# schemat.net
KiCad netlist of a schematic drawn in Altium Designer
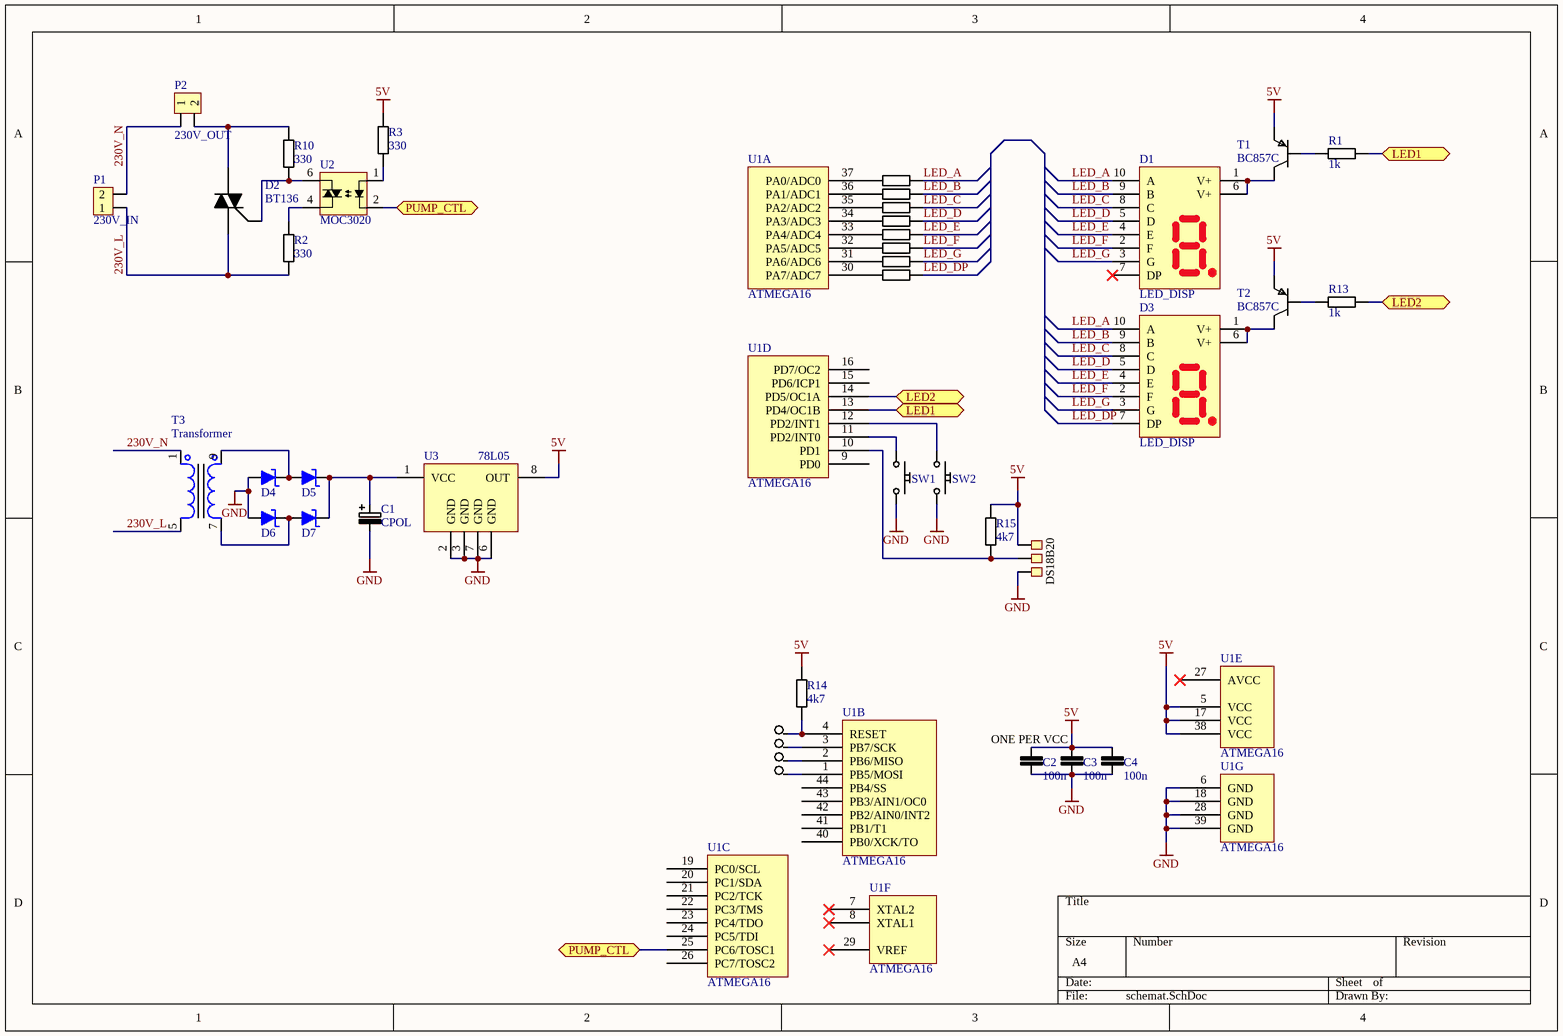
[diagram p0: schemat.SchDoc]

(export (version "E")
  (design (tool "Eeschema 10.0.6"))
  (components
    (comp (ref "C1") (value "CPOL") (footprint "Cap10/5mm") (libsource (lib "A4WP") (part "CPOL")))
    (comp (ref "C2")
      (value "100n")
      (footprint "0805C")
      (description "Kondensator")
      (libsource (lib "iMed24") (part "C"))
    )
    (comp (ref "C3")
      (value "100n")
      (footprint "0805C")
      (description "Kondensator")
      (libsource (lib "iMed24") (part "C"))
    )
    (comp (ref "C4")
      (value "100n")
      (footprint "0805C")
      (description "Kondensator")
      (libsource (lib "iMed24") (part "C"))
    )
    (comp (ref "D1")
      (value "LED_DISP")
      (footprint "LED_DISP")
      (libsource (lib "BibliotekiAltium") (part "LED_DISP"))
    )
    (comp (ref "D2") (value "BT136") (footprint "TO220") (libsource (lib "BibliotekiAltium") (part "BT136")))
    (comp (ref "D3")
      (value "LED_DISP")
      (footprint "LED_DISP")
      (libsource (lib "BibliotekiAltium") (part "LED_DISP"))
    )
    (comp (ref "D4") (value "Schottky") (footprint "SOD128") (libsource (lib "gan_mgr") (part "Schottky")))
    (comp (ref "D5") (value "Schottky") (footprint "SOD128") (libsource (lib "gan_mgr") (part "Schottky")))
    (comp (ref "D6") (value "Schottky") (footprint "SOD128") (libsource (lib "gan_mgr") (part "Schottky")))
    (comp (ref "D7") (value "Schottky") (footprint "SOD128") (libsource (lib "gan_mgr") (part "Schottky")))
    (comp (ref "P1")
      (value "230V_IN")
      (footprint "ARK2")
      (description "5mm")
      (libsource (lib "gan_mgr") (part "ARK2"))
    )
    (comp (ref "P2")
      (value "230V_OUT")
      (footprint "ARK2")
      (description "5mm")
      (libsource (lib "") (part "ARK2_1"))
    )
    (comp (ref "P3") (value "PAD") (footprint "PAD1.5") (libsource (lib "KWP") (part "PAD")))
    (comp (ref "P4") (value "PAD") (footprint "PAD1.5") (libsource (lib "KWP") (part "PAD")))
    (comp (ref "P5") (value "PAD") (footprint "PAD1.5") (libsource (lib "KWP") (part "PAD")))
    (comp (ref "P6") (value "PAD") (footprint "PAD1.5") (libsource (lib "KWP") (part "PAD")))
    (comp (ref "P7")
      (value "PAD_THT")
      (footprint "PAD_0.8mm")
      (libsource (lib "BibliotekiAltium") (part "PAD_THT"))
    )
    (comp (ref "P8")
      (value "PAD_THT")
      (footprint "PAD_0.8mm")
      (libsource (lib "BibliotekiAltium") (part "PAD_THT"))
    )
    (comp (ref "P9")
      (value "PAD_THT")
      (footprint "PAD_0.8mm")
      (libsource (lib "BibliotekiAltium") (part "PAD_THT"))
    )
    (comp (ref "R1")
      (value "1k")
      (footprint "0805R")
      (description "Rezystor")
      (libsource (lib "iMed24") (part "R"))
    )
    (comp (ref "R2")
      (value "330")
      (footprint "0805R")
      (description "Rezystor")
      (libsource (lib "") (part "R_1"))
    )
    (comp (ref "R3")
      (value "330")
      (footprint "0805R")
      (description "Rezystor")
      (libsource (lib "iMed24") (part "R"))
    )
    (comp (ref "R4")
      (value "220")
      (footprint "0805R")
      (description "Rezystor")
      (libsource (lib "iMed24") (part "R"))
    )
    (comp (ref "R5")
      (value "220")
      (footprint "0805R")
      (description "Rezystor")
      (libsource (lib "iMed24") (part "R"))
    )
    (comp (ref "R6")
      (value "220")
      (footprint "0805R")
      (description "Rezystor")
      (libsource (lib "iMed24") (part "R"))
    )
    (comp (ref "R7")
      (value "220")
      (footprint "0805R")
      (description "Rezystor")
      (libsource (lib "iMed24") (part "R"))
    )
    (comp (ref "R8")
      (value "220")
      (footprint "0805R")
      (description "Rezystor")
      (libsource (lib "iMed24") (part "R"))
    )
    (comp (ref "R9")
      (value "220")
      (footprint "0805R")
      (description "Rezystor")
      (libsource (lib "iMed24") (part "R"))
    )
    (comp (ref "R10")
      (value "330")
      (footprint "0805R")
      (description "Rezystor")
      (libsource (lib "") (part "R_1"))
    )
    (comp (ref "R11")
      (value "220")
      (footprint "0805R")
      (description "Rezystor")
      (libsource (lib "iMed24") (part "R"))
    )
    (comp (ref "R12")
      (value "220")
      (footprint "0805R")
      (description "Rezystor")
      (libsource (lib "iMed24") (part "R"))
    )
    (comp (ref "R13")
      (value "1k")
      (footprint "0805R")
      (description "Rezystor")
      (libsource (lib "iMed24") (part "R"))
    )
    (comp (ref "R14")
      (value "4k7")
      (footprint "0805R")
      (description "Rezystor")
      (libsource (lib "") (part "R_1"))
    )
    (comp (ref "R15")
      (value "4k7")
      (footprint "0805R")
      (description "Rezystor")
      (libsource (lib "") (part "R_1"))
    )
    (comp (ref "SW1")
      (value "SW 5mm 1,5N SMD")
      (footprint "SW5SMD")
      (description "Microswitch")
      (libsource (lib "iMed24") (part "SW 5mm 1,5N SMD"))
    )
    (comp (ref "SW2")
      (value "SW 5mm 1,5N SMD")
      (footprint "SW5SMD")
      (description "Microswitch")
      (libsource (lib "iMed24") (part "SW 5mm 1,5N SMD"))
    )
    (comp (ref "T1")
      (value "BC857C")
      (footprint "SOT23-3")
      (description "PNP (45V/0.1A)")
      (libsource (lib "Transistor") (part "BC857C"))
    )
    (comp (ref "T2")
      (value "BC857C")
      (footprint "SOT23-3")
      (description "PNP (45V/0.1A)")
      (libsource (lib "Transistor") (part "BC857C"))
    )
    (comp (ref "T3")
      (value "Transformer")
      (footprint "TSZZ4.5/017M")
      (libsource (lib "BibliotekiAltium") (part "Transformer"))
    )
    (comp (ref "U1")
      (value "ATMEGA16")
      (footprint "TQFP44")
      (libsource (lib "BibliotekiAltium") (part "ATMEGA16"))
    )
    (comp (ref "U2")
      (value "MOC3020")
      (footprint "DIP6")
      (libsource (lib "BibliotekiAltium") (part "MOC3020"))
    )
    (comp (ref "U3") (value "78L05") (footprint "SOIC8") (libsource (lib "BibliotekiAltium") (part "78L05")))
  )
  (nets
    (net (code "1") (name "/230V_L") (class "Default")
      (node (ref "D2") (pin "1") (pinfunction "T1_1") (pintype "passive"))
      (node (ref "P1") (pin "1") (pinfunction "1_1") (pintype "passive"))
      (node (ref "R2") (pin "2") (pinfunction "2_2") (pintype "passive"))
      (node (ref "T3") (pin "5") (pinfunction "5_5") (pintype "passive"))
    )
    (net (code "2") (name "/230V_N") (class "Default")
      (node (ref "P1") (pin "2") (pinfunction "2_2") (pintype "passive"))
      (node (ref "P2") (pin "1") (pinfunction "1_1") (pintype "passive"))
      (node (ref "T3") (pin "1") (pinfunction "1_1") (pintype "passive"))
    )
    (net (code "3") (name "/LED1") (class "Default")
      (node (ref "R1") (pin "2") (pinfunction "2_2") (pintype "passive"))
      (node (ref "U1") (pin "13") (pinfunction "PD4/OC1B_13") (pintype "passive"))
    )
    (net (code "4") (name "/LED2") (class "Default")
      (node (ref "R13") (pin "2") (pinfunction "2_2") (pintype "passive"))
      (node (ref "U1") (pin "14") (pinfunction "PD5/OC1A_14") (pintype "passive"))
    )
    (net (code "5") (name "/LED_A") (class "Default")
      (node (ref "D1") (pin "10") (pinfunction "A_10") (pintype "passive"))
      (node (ref "D3") (pin "10") (pinfunction "A_10") (pintype "passive"))
      (node (ref "R4") (pin "2") (pinfunction "2_2") (pintype "passive"))
    )
    (net (code "6") (name "/LED_B") (class "Default")
      (node (ref "D1") (pin "9") (pinfunction "B_9") (pintype "passive"))
      (node (ref "D3") (pin "9") (pinfunction "B_9") (pintype "passive"))
      (node (ref "R5") (pin "2") (pinfunction "2_2") (pintype "passive"))
    )
    (net (code "7") (name "/LED_C") (class "Default")
      (node (ref "D1") (pin "8") (pinfunction "C_8") (pintype "passive"))
      (node (ref "D3") (pin "8") (pinfunction "C_8") (pintype "passive"))
      (node (ref "R6") (pin "2") (pinfunction "2_2") (pintype "passive"))
    )
    (net (code "8") (name "/LED_D") (class "Default")
      (node (ref "D1") (pin "5") (pinfunction "D_5") (pintype "passive"))
      (node (ref "D3") (pin "5") (pinfunction "D_5") (pintype "passive"))
      (node (ref "R7") (pin "2") (pinfunction "2_2") (pintype "passive"))
    )
    (net (code "9") (name "/LED_DP") (class "Default")
      (node (ref "D3") (pin "7") (pinfunction "DP_7") (pintype "passive"))
      (node (ref "R12") (pin "2") (pinfunction "2_2") (pintype "passive"))
    )
    (net (code "10") (name "/LED_E") (class "Default")
      (node (ref "D1") (pin "4") (pinfunction "E_4") (pintype "passive"))
      (node (ref "D3") (pin "4") (pinfunction "E_4") (pintype "passive"))
      (node (ref "R8") (pin "2") (pinfunction "2_2") (pintype "passive"))
    )
    (net (code "11") (name "/LED_F") (class "Default")
      (node (ref "D1") (pin "2") (pinfunction "F_2") (pintype "passive"))
      (node (ref "D3") (pin "2") (pinfunction "F_2") (pintype "passive"))
      (node (ref "R9") (pin "2") (pinfunction "2_2") (pintype "passive"))
    )
    (net (code "12") (name "/LED_G") (class "Default")
      (node (ref "D1") (pin "3") (pinfunction "G_3") (pintype "passive"))
      (node (ref "D3") (pin "3") (pinfunction "G_3") (pintype "passive"))
      (node (ref "R11") (pin "2") (pinfunction "2_2") (pintype "passive"))
    )
    (net (code "13") (name "/PUMP_CTL") (class "Default")
      (node (ref "U1") (pin "25") (pinfunction "PC6/TOSC1_25") (pintype "passive"))
      (node (ref "U2") (pin "2") (pinfunction "2_2") (pintype "passive"))
    )
    (net (code "14") (name "5V") (class "Default")
      (node (ref "C2") (pin "1") (pinfunction "1_1") (pintype "passive"))
      (node (ref "C3") (pin "1") (pinfunction "1_1") (pintype "passive"))
      (node (ref "C4") (pin "1") (pinfunction "1_1") (pintype "passive"))
      (node (ref "P7") (pin "1") (pinfunction "1_1") (pintype "power_in"))
      (node (ref "R14") (pin "1") (pinfunction "1_1") (pintype "passive"))
      (node (ref "R15") (pin "1") (pinfunction "1_1") (pintype "passive"))
      (node (ref "R3") (pin "2") (pinfunction "2_2") (pintype "passive"))
      (node (ref "T1") (pin "3") (pinfunction "C_3") (pintype "passive"))
      (node (ref "T2") (pin "3") (pinfunction "C_3") (pintype "passive"))
      (node (ref "U1") (pin "17") (pinfunction "VCC_17") (pintype "passive"))
      (node (ref "U1") (pin "38") (pinfunction "VCC_38") (pintype "passive"))
      (node (ref "U1") (pin "5") (pinfunction "VCC_5") (pintype "passive"))
      (node (ref "U3") (pin "8") (pinfunction "OUT_8") (pintype "passive"))
    )
    (net (code "15") (name "GND") (class "Default")
      (node (ref "C1") (pin "1") (pinfunction "1_1") (pintype "passive"))
      (node (ref "C2") (pin "2") (pinfunction "2_2") (pintype "passive"))
      (node (ref "C3") (pin "2") (pinfunction "2_2") (pintype "passive"))
      (node (ref "C4") (pin "2") (pinfunction "2_2") (pintype "passive"))
      (node (ref "D4") (pin "2") (pinfunction "A_2") (pintype "passive"))
      (node (ref "D6") (pin "2") (pinfunction "A_2") (pintype "passive"))
      (node (ref "P9") (pin "1") (pinfunction "1_1") (pintype "power_in"))
      (node (ref "SW1") (pin "1") (pinfunction "1_1") (pintype "passive"))
      (node (ref "SW2") (pin "1") (pinfunction "1_1") (pintype "passive"))
      (node (ref "U1") (pin "18") (pinfunction "GND_18") (pintype "passive"))
      (node (ref "U1") (pin "28") (pinfunction "GND_28") (pintype "passive"))
      (node (ref "U1") (pin "39") (pinfunction "GND_39") (pintype "passive"))
      (node (ref "U1") (pin "6") (pinfunction "GND_6") (pintype "passive"))
      (node (ref "U3") (pin "2") (pinfunction "GND_2") (pintype "passive"))
      (node (ref "U3") (pin "3") (pinfunction "GND_3") (pintype "passive"))
      (node (ref "U3") (pin "6") (pinfunction "GND_6") (pintype "passive"))
      (node (ref "U3") (pin "7") (pinfunction "GND_7") (pintype "passive"))
    )
    (net (code "16") (name "Net-(D2-G)") (class "Default")
      (node (ref "D2") (pin "3") (pinfunction "G_3") (pintype "passive"))
      (node (ref "R10") (pin "2") (pinfunction "2_2") (pintype "passive"))
      (node (ref "U2") (pin "6") (pinfunction "6_6") (pintype "passive"))
    )
    (net (code "17") (name "Net-(D2-T2)") (class "Default")
      (node (ref "D2") (pin "2") (pinfunction "T2_2") (pintype "passive"))
      (node (ref "P2") (pin "2") (pinfunction "2_2") (pintype "passive"))
      (node (ref "R10") (pin "1") (pinfunction "1_1") (pintype "passive"))
    )
    (net (code "18") (name "Net-(D4-K)") (class "Default")
      (node (ref "D4") (pin "1") (pinfunction "K_1") (pintype "passive"))
      (node (ref "D5") (pin "2") (pinfunction "A_2") (pintype "passive"))
      (node (ref "T3") (pin "9") (pinfunction "9_9") (pintype "passive"))
    )
    (net (code "19") (name "Net-(D5-K)") (class "Default")
      (node (ref "C1") (pin "2") (pinfunction "2_2") (pintype "passive"))
      (node (ref "D5") (pin "1") (pinfunction "K_1") (pintype "passive"))
      (node (ref "D7") (pin "1") (pinfunction "K_1") (pintype "passive"))
      (node (ref "U3") (pin "1") (pinfunction "VCC_1") (pintype "passive"))
    )
    (net (code "20") (name "Net-(D6-K)") (class "Default")
      (node (ref "D6") (pin "1") (pinfunction "K_1") (pintype "passive"))
      (node (ref "D7") (pin "2") (pinfunction "A_2") (pintype "passive"))
      (node (ref "T3") (pin "7") (pinfunction "7_7") (pintype "passive"))
    )
    (net (code "21") (name "Net-(R2-Pad1)") (class "Default")
      (node (ref "R2") (pin "1") (pinfunction "1_1") (pintype "passive"))
      (node (ref "U2") (pin "4") (pinfunction "4_4") (pintype "passive"))
    )
    (net (code "22") (name "Net-(R3-Pad1)") (class "Default")
      (node (ref "R3") (pin "1") (pinfunction "1_1") (pintype "passive"))
      (node (ref "U2") (pin "1") (pinfunction "1_1") (pintype "passive"))
    )
    (net (code "23") (name "Net-(T1-B)") (class "Default")
      (node (ref "R1") (pin "1") (pinfunction "1_1") (pintype "passive"))
      (node (ref "T1") (pin "1") (pinfunction "B_1") (pintype "passive"))
    )
    (net (code "24") (name "Net-(T1-E)") (class "Default")
      (node (ref "D1") (pin "1") (pinfunction "V+_1") (pintype "passive"))
      (node (ref "D1") (pin "6") (pinfunction "V+_6") (pintype "passive"))
      (node (ref "T1") (pin "2") (pinfunction "E_2") (pintype "passive"))
    )
    (net (code "25") (name "Net-(T2-B)") (class "Default")
      (node (ref "R13") (pin "1") (pinfunction "1_1") (pintype "passive"))
      (node (ref "T2") (pin "1") (pinfunction "B_1") (pintype "passive"))
    )
    (net (code "26") (name "Net-(T2-E)") (class "Default")
      (node (ref "D3") (pin "1") (pinfunction "V+_1") (pintype "passive"))
      (node (ref "D3") (pin "6") (pinfunction "V+_6") (pintype "passive"))
      (node (ref "T2") (pin "2") (pinfunction "E_2") (pintype "passive"))
    )
    (net (code "27") (name "Net-(U1A-PA0{slash}ADC0)") (class "Default")
      (node (ref "R4") (pin "1") (pinfunction "1_1") (pintype "passive"))
      (node (ref "U1") (pin "37") (pinfunction "PA0/ADC0_37") (pintype "passive"))
    )
    (net (code "28") (name "Net-(U1A-PA1{slash}ADC1)") (class "Default")
      (node (ref "R5") (pin "1") (pinfunction "1_1") (pintype "passive"))
      (node (ref "U1") (pin "36") (pinfunction "PA1/ADC1_36") (pintype "passive"))
    )
    (net (code "29") (name "Net-(U1A-PA2{slash}ADC2)") (class "Default")
      (node (ref "R6") (pin "1") (pinfunction "1_1") (pintype "passive"))
      (node (ref "U1") (pin "35") (pinfunction "PA2/ADC2_35") (pintype "passive"))
    )
    (net (code "30") (name "Net-(U1A-PA3{slash}ADC3)") (class "Default")
      (node (ref "R7") (pin "1") (pinfunction "1_1") (pintype "passive"))
      (node (ref "U1") (pin "34") (pinfunction "PA3/ADC3_34") (pintype "passive"))
    )
    (net (code "31") (name "Net-(U1A-PA4{slash}ADC4)") (class "Default")
      (node (ref "R8") (pin "1") (pinfunction "1_1") (pintype "passive"))
      (node (ref "U1") (pin "33") (pinfunction "PA4/ADC4_33") (pintype "passive"))
    )
    (net (code "32") (name "Net-(U1A-PA5{slash}ADC5)") (class "Default")
      (node (ref "R9") (pin "1") (pinfunction "1_1") (pintype "passive"))
      (node (ref "U1") (pin "32") (pinfunction "PA5/ADC5_32") (pintype "passive"))
    )
    (net (code "33") (name "Net-(U1A-PA6{slash}ADC6)") (class "Default")
      (node (ref "R11") (pin "1") (pinfunction "1_1") (pintype "passive"))
      (node (ref "U1") (pin "31") (pinfunction "PA6/ADC6_31") (pintype "passive"))
    )
    (net (code "34") (name "Net-(U1A-PA7{slash}ADC7)") (class "Default")
      (node (ref "R12") (pin "1") (pinfunction "1_1") (pintype "passive"))
      (node (ref "U1") (pin "30") (pinfunction "PA7/ADC7_30") (pintype "passive"))
    )
    (net (code "35") (name "Net-(U1B-PB5{slash}MOSI)") (class "Default")
      (node (ref "P6") (pin "1") (pinfunction "1_1") (pintype "passive"))
      (node (ref "U1") (pin "1") (pinfunction "PB5/MOSI_1") (pintype "passive"))
    )
    (net (code "36") (name "Net-(U1B-PB6{slash}MISO)") (class "Default")
      (node (ref "P5") (pin "1") (pinfunction "1_1") (pintype "passive"))
      (node (ref "U1") (pin "2") (pinfunction "PB6/MISO_2") (pintype "passive"))
    )
    (net (code "37") (name "Net-(U1B-PB7{slash}SCK)") (class "Default")
      (node (ref "P4") (pin "1") (pinfunction "1_1") (pintype "passive"))
      (node (ref "U1") (pin "3") (pinfunction "PB7/SCK_3") (pintype "passive"))
    )
    (net (code "38") (name "Net-(U1B-RESET)") (class "Default")
      (node (ref "P3") (pin "1") (pinfunction "1_1") (pintype "passive"))
      (node (ref "R14") (pin "2") (pinfunction "2_2") (pintype "passive"))
      (node (ref "U1") (pin "4") (pinfunction "RESET_4") (pintype "passive"))
    )
    (net (code "39") (name "Net-(U1D-PD1)") (class "Default")
      (node (ref "P8") (pin "1") (pinfunction "1_1") (pintype "power_in"))
      (node (ref "R15") (pin "2") (pinfunction "2_2") (pintype "passive"))
      (node (ref "U1") (pin "10") (pinfunction "PD1_10") (pintype "passive"))
    )
    (net (code "40") (name "Net-(U1D-PD2{slash}INT0)") (class "Default")
      (node (ref "SW1") (pin "2") (pinfunction "2_2") (pintype "passive"))
      (node (ref "U1") (pin "11") (pinfunction "PD2/INT0_11") (pintype "passive"))
    )
    (net (code "41") (name "Net-(U1D-PD2{slash}INT1)") (class "Default")
      (node (ref "SW2") (pin "2") (pinfunction "2_2") (pintype "passive"))
      (node (ref "U1") (pin "12") (pinfunction "PD2/INT1_12") (pintype "passive"))
    )
    (net (code "42") (name "unconnected-(D1-DP-Pad7)") (class "Default")
      (node (ref "D1") (pin "7") (pinfunction "DP_7") (pintype "passive+no_connect"))
    )
    (net (code "43") (name "unconnected-(U1B-PB0{slash}XCK{slash}TO-Pad40)") (class "Default")
      (node (ref "U1") (pin "40") (pinfunction "PB0/XCK/TO_40") (pintype "passive"))
    )
    (net (code "44") (name "unconnected-(U1B-PB1{slash}T1-Pad41)") (class "Default")
      (node (ref "U1") (pin "41") (pinfunction "PB1/T1_41") (pintype "passive"))
    )
    (net (code "45") (name "unconnected-(U1B-PB2{slash}AIN0{slash}INT2-Pad42)") (class "Default")
      (node (ref "U1") (pin "42") (pinfunction "PB2/AIN0/INT2_42") (pintype "passive"))
    )
    (net (code "46") (name "unconnected-(U1B-PB3{slash}AIN1{slash}OC0-Pad43)") (class "Default")
      (node (ref "U1") (pin "43") (pinfunction "PB3/AIN1/OC0_43") (pintype "passive"))
    )
    (net (code "47") (name "unconnected-(U1B-PB4{slash}SS-Pad44)") (class "Default")
      (node (ref "U1") (pin "44") (pinfunction "PB4/SS_44") (pintype "passive"))
    )
    (net (code "48") (name "unconnected-(U1C-PC0{slash}SCL-Pad19)") (class "Default")
      (node (ref "U1") (pin "19") (pinfunction "PC0/SCL_19") (pintype "passive"))
    )
    (net (code "49") (name "unconnected-(U1C-PC1{slash}SDA-Pad20)") (class "Default")
      (node (ref "U1") (pin "20") (pinfunction "PC1/SDA_20") (pintype "passive"))
    )
    (net (code "50") (name "unconnected-(U1C-PC2{slash}TCK-Pad21)") (class "Default")
      (node (ref "U1") (pin "21") (pinfunction "PC2/TCK_21") (pintype "passive"))
    )
    (net (code "51") (name "unconnected-(U1C-PC3{slash}TMS-Pad22)") (class "Default")
      (node (ref "U1") (pin "22") (pinfunction "PC3/TMS_22") (pintype "passive"))
    )
    (net (code "52") (name "unconnected-(U1C-PC4{slash}TDO-Pad23)") (class "Default")
      (node (ref "U1") (pin "23") (pinfunction "PC4/TDO_23") (pintype "passive"))
    )
    (net (code "53") (name "unconnected-(U1C-PC5{slash}TDI-Pad24)") (class "Default")
      (node (ref "U1") (pin "24") (pinfunction "PC5/TDI_24") (pintype "passive"))
    )
    (net (code "54") (name "unconnected-(U1C-PC7{slash}TOSC2-Pad26)") (class "Default")
      (node (ref "U1") (pin "26") (pinfunction "PC7/TOSC2_26") (pintype "passive"))
    )
    (net (code "55") (name "unconnected-(U1D-PD0-Pad9)") (class "Default")
      (node (ref "U1") (pin "9") (pinfunction "PD0_9") (pintype "passive"))
    )
    (net (code "56") (name "unconnected-(U1D-PD6{slash}ICP1-Pad15)") (class "Default")
      (node (ref "U1") (pin "15") (pinfunction "PD6/ICP1_15") (pintype "passive"))
    )
    (net (code "57") (name "unconnected-(U1D-PD7{slash}OC2-Pad16)") (class "Default")
      (node (ref "U1") (pin "16") (pinfunction "PD7/OC2_16") (pintype "passive"))
    )
    (net (code "58") (name "unconnected-(U1E-AVCC-Pad27)") (class "Default")
      (node (ref "U1") (pin "27") (pinfunction "AVCC_27") (pintype "passive+no_connect"))
    )
    (net (code "59") (name "unconnected-(U1F-VREF-Pad29)") (class "Default")
      (node (ref "U1") (pin "29") (pinfunction "VREF_29") (pintype "passive+no_connect"))
    )
    (net (code "60") (name "unconnected-(U1F-XTAL1-Pad8)") (class "Default")
      (node (ref "U1") (pin "8") (pinfunction "XTAL1_8") (pintype "passive+no_connect"))
    )
    (net (code "61") (name "unconnected-(U1F-XTAL2-Pad7)") (class "Default")
      (node (ref "U1") (pin "7") (pinfunction "XTAL2_7") (pintype "passive+no_connect"))
    )
  )
)
